# LED_Connector.net
KiCad netlist of a schematic drawn in Altium Designer
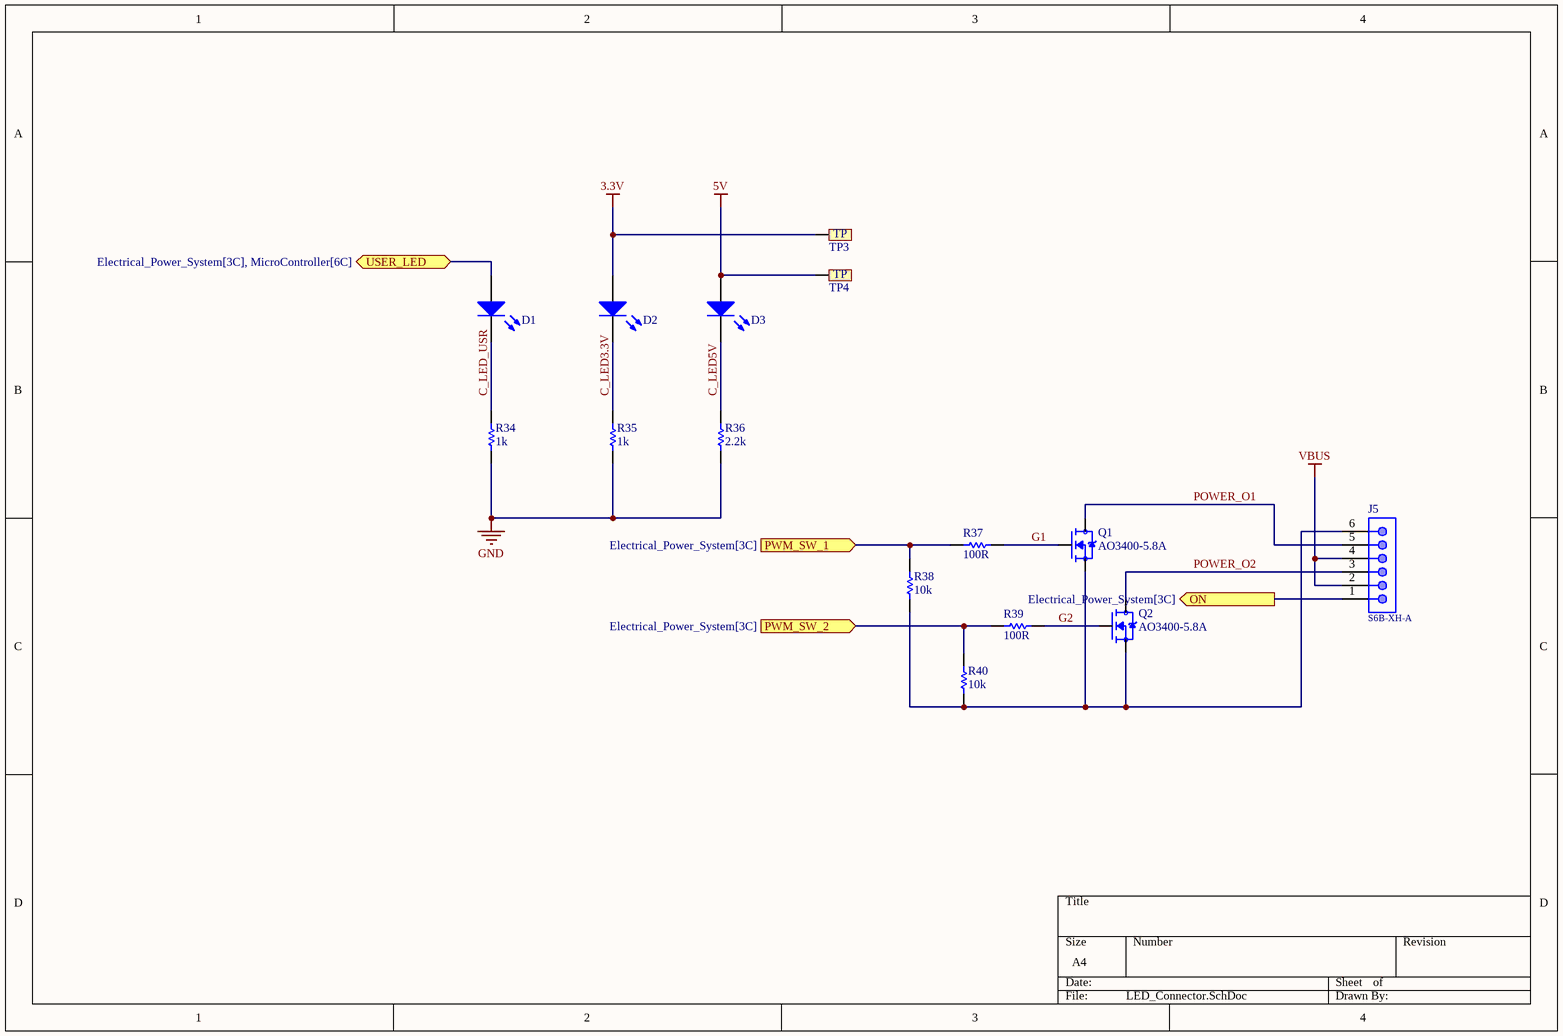
[diagram p0: LED_Connector.SchDoc]

(export (version "E")
  (design (tool "Eeschema 10.0.6"))
  (components
    (comp (ref "D1")
      (value "LED SMD")
      (footprint "LED_0805_Blue")
      (description "LED")
      (libsource (lib "PIF_Library") (part "LED SMD"))
    )
    (comp (ref "D2")
      (value "LED SMD")
      (footprint "LED_0805_Blue")
      (description "LED")
      (libsource (lib "PIF_Library") (part "LED SMD"))
    )
    (comp (ref "D3")
      (value "LED SMD")
      (footprint "LED_0805_Blue")
      (description "LED")
      (libsource (lib "PIF_Library") (part "LED SMD"))
    )
    (comp (ref "J5")
      (value "S6B-XH-A")
      (footprint "S6B-XH-A")
      (description "WR-PHD Pin Header, THT, pitch 2.54mm, Single Row, Angled, 6p")
      (fields
        (field (name "MANUFACTURER PART NUMBER") "61300611021")
        (field (name "MANUFACTURER") "Wurth Elektronik")
      )
      (libsource (lib "EPS_Board_Lib") (part "S6B-XH-A"))
    )
    (comp (ref "Q1")
      (value "AO3400-5.8A")
      (footprint "SOT95P260X140-3N")
      (description "N-Channel 30 V 5.8A (Ta) 1.5W (Ta) Surface Mount SOT-23")
      (fields (field (name "MF") "MDD"))
      (libsource (lib "EPS_Board_Lib") (part "AO3400-5.8A"))
    )
    (comp (ref "Q2")
      (value "AO3400-5.8A")
      (footprint "SOT95P260X140-3N")
      (description "N-Channel 30 V 5.8A (Ta) 1.5W (Ta) Surface Mount SOT-23")
      (fields (field (name "MF") "MDD"))
      (libsource (lib "EPS_Board_Lib") (part "AO3400-5.8A"))
    )
    (comp (ref "R34")
      (value "1k")
      (footprint "RES-SM-0805")
      (description "Resistor")
      (fields (field (name "Comment") "RESISTOR SMD"))
      (libsource (lib "PIF_Library") (part "RESISTOR SMD"))
    )
    (comp (ref "R35")
      (value "1k")
      (footprint "RES-SM-0805")
      (description "Resistor")
      (fields (field (name "Comment") "RESISTOR SMD"))
      (libsource (lib "PIF_Library") (part "RESISTOR SMD"))
    )
    (comp (ref "R36")
      (value "2.2k")
      (footprint "RES-SM-0805")
      (description "Resistor")
      (fields (field (name "Comment") "RESISTOR SMD"))
      (libsource (lib "PIF_Library") (part "RESISTOR SMD"))
    )
    (comp (ref "R37")
      (value "100R")
      (footprint "RES-SM-0805")
      (description "Resistor")
      (fields (field (name "Comment") "RESISTOR SMD"))
      (libsource (lib "PIF_Library") (part "RESISTOR SMD"))
    )
    (comp (ref "R38")
      (value "10k")
      (footprint "RES-SM-0805")
      (description "Resistor")
      (fields (field (name "Comment") "RESISTOR SMD"))
      (libsource (lib "PIF_Library") (part "RESISTOR SMD"))
    )
    (comp (ref "R39")
      (value "100R")
      (footprint "RES-SM-0805")
      (description "Resistor")
      (fields (field (name "Comment") "RESISTOR SMD"))
      (libsource (lib "PIF_Library") (part "RESISTOR SMD"))
    )
    (comp (ref "R40")
      (value "10k")
      (footprint "RES-SM-0805")
      (description "Resistor")
      (fields (field (name "Comment") "RESISTOR SMD"))
      (libsource (lib "PIF_Library") (part "RESISTOR SMD"))
    )
    (comp (ref "TP3")
      (value "Test Point")
      (footprint "TP")
      (libsource (lib "PIF_Library") (part "Test Point"))
    )
    (comp (ref "TP4")
      (value "Test Point")
      (footprint "TP")
      (libsource (lib "PIF_Library") (part "Test Point"))
    )
  )
  (nets
    (net (code "1") (name "/C_LED3.3V") (class "Default")
      (node (ref "D2") (pin "2") (pinfunction "K_2") (pintype "passive"))
      (node (ref "R35") (pin "1") (pinfunction "1_1") (pintype "passive"))
    )
    (net (code "2") (name "/C_LED5V") (class "Default")
      (node (ref "D3") (pin "2") (pinfunction "K_2") (pintype "passive"))
      (node (ref "R36") (pin "1") (pinfunction "1_1") (pintype "passive"))
    )
    (net (code "3") (name "/C_LED_USR") (class "Default")
      (node (ref "D1") (pin "2") (pinfunction "K_2") (pintype "passive"))
      (node (ref "R34") (pin "1") (pinfunction "1_1") (pintype "passive"))
    )
    (net (code "4") (name "/G1") (class "Default")
      (node (ref "Q1") (pin "1") (pinfunction "G_1") (pintype "passive"))
      (node (ref "R37") (pin "2") (pinfunction "2_2") (pintype "passive"))
    )
    (net (code "5") (name "/G2") (class "Default")
      (node (ref "Q2") (pin "1") (pinfunction "G_1") (pintype "passive"))
      (node (ref "R39") (pin "2") (pinfunction "2_2") (pintype "passive"))
    )
    (net (code "6") (name "/ON") (class "Default")
      (node (ref "J5") (pin "1") (pinfunction "1_1") (pintype "passive"))
    )
    (net (code "7") (name "/POWER_O1") (class "Default")
      (node (ref "J5") (pin "5") (pinfunction "5_5") (pintype "passive"))
      (node (ref "Q1") (pin "3") (pinfunction "D_3") (pintype "passive"))
    )
    (net (code "8") (name "/POWER_O2") (class "Default")
      (node (ref "J5") (pin "3") (pinfunction "3_3") (pintype "passive"))
      (node (ref "Q2") (pin "3") (pinfunction "D_3") (pintype "passive"))
    )
    (net (code "9") (name "/PWM_SW_1") (class "Default")
      (node (ref "R37") (pin "1") (pinfunction "1_1") (pintype "passive"))
      (node (ref "R38") (pin "1") (pinfunction "1_1") (pintype "passive"))
    )
    (net (code "10") (name "/PWM_SW_2") (class "Default")
      (node (ref "R39") (pin "1") (pinfunction "1_1") (pintype "passive"))
      (node (ref "R40") (pin "1") (pinfunction "1_1") (pintype "passive"))
    )
    (net (code "11") (name "/USER_LED") (class "Default")
      (node (ref "D1") (pin "1") (pinfunction "A_1") (pintype "passive"))
    )
    (net (code "12") (name "3.3V") (class "Default")
      (node (ref "D2") (pin "1") (pinfunction "A_1") (pintype "passive"))
      (node (ref "TP3") (pin "TP1") (pinfunction "0_TP1") (pintype "passive"))
    )
    (net (code "13") (name "5V") (class "Default")
      (node (ref "D3") (pin "1") (pinfunction "A_1") (pintype "passive"))
      (node (ref "TP4") (pin "TP1") (pinfunction "0_TP1") (pintype "passive"))
    )
    (net (code "14") (name "GND") (class "Default")
      (node (ref "R34") (pin "2") (pinfunction "2_2") (pintype "passive"))
      (node (ref "R35") (pin "2") (pinfunction "2_2") (pintype "passive"))
      (node (ref "R36") (pin "2") (pinfunction "2_2") (pintype "passive"))
    )
    (net (code "15") (name "Net-(Q1-S)") (class "Default")
      (node (ref "J5") (pin "6") (pinfunction "6_6") (pintype "passive"))
      (node (ref "Q1") (pin "2") (pinfunction "S_2") (pintype "passive"))
      (node (ref "Q2") (pin "2") (pinfunction "S_2") (pintype "passive"))
      (node (ref "R38") (pin "2") (pinfunction "2_2") (pintype "passive"))
      (node (ref "R40") (pin "2") (pinfunction "2_2") (pintype "passive"))
    )
    (net (code "16") (name "VBUS") (class "Default")
      (node (ref "J5") (pin "2") (pinfunction "2_2") (pintype "passive"))
      (node (ref "J5") (pin "4") (pinfunction "4_4") (pintype "passive"))
    )
  )
)
